# Weight-X.net
KiCad netlist of a schematic drawn in EAGLE
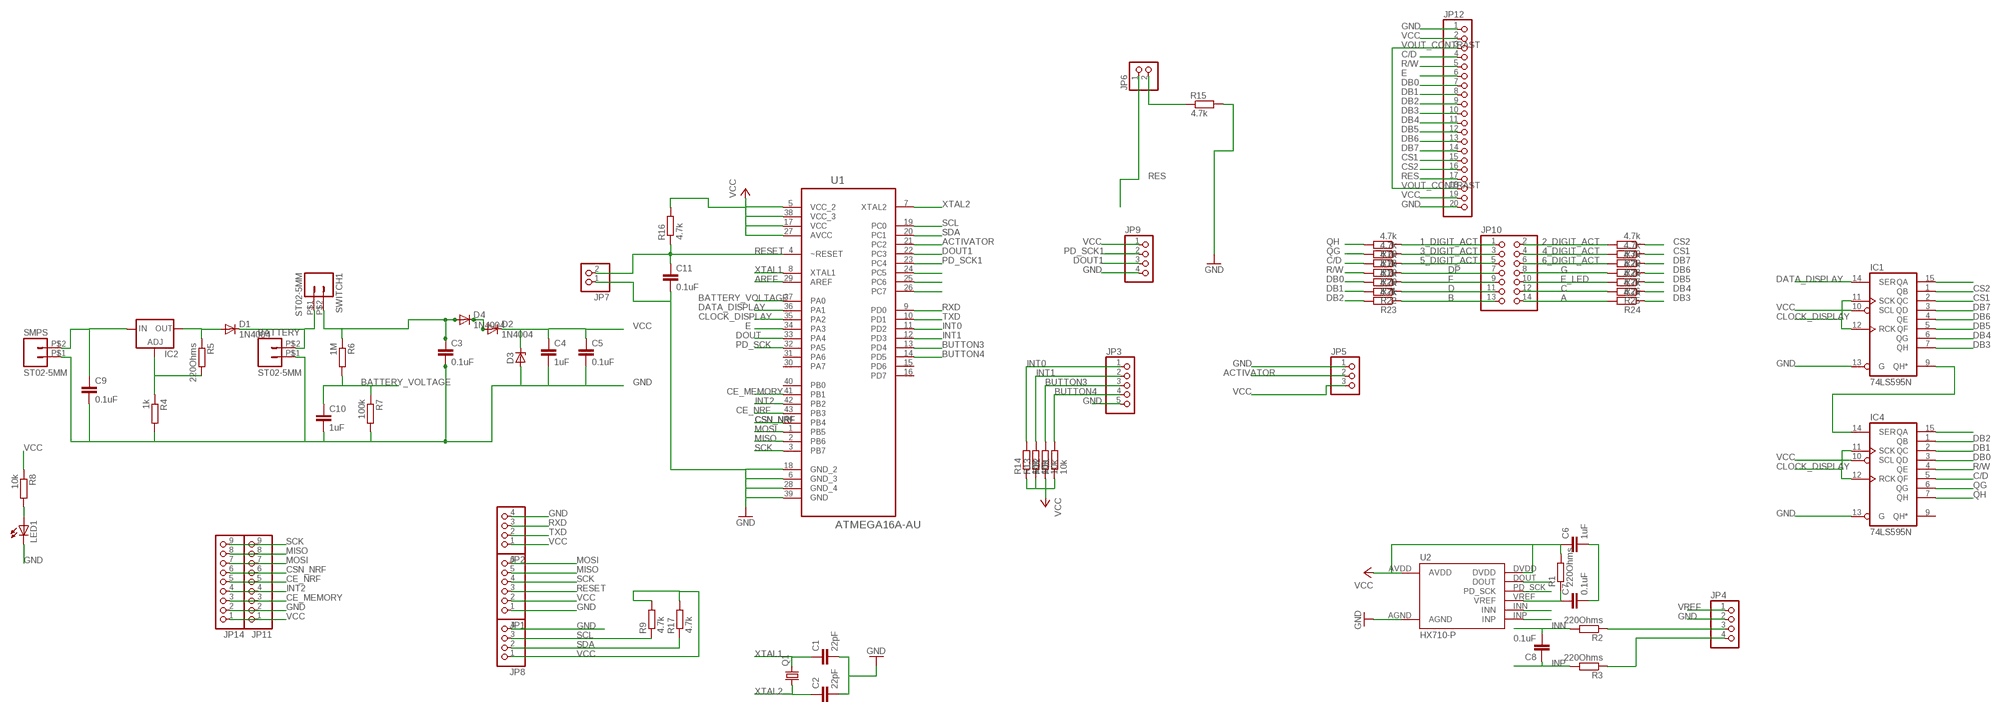
[diagram p0: schematic, sheet 1]

(export (version "E")
  (design (tool "Eeschema 10.0.6"))
  (components
    (comp (ref "BATTERY")
      (value "ST02-5MM")
      (footprint "eagle-import:EK500V-02P")
      (libsource (lib "eagle-import") (part "ST02-5MM"))
    )
    (comp (ref "C1")
      (value "22pF")
      (footprint "eagle-import:C2.5-2")
      (libsource (lib "eagle-import") (part "C2.5/2"))
    )
    (comp (ref "C2")
      (value "22pF")
      (footprint "eagle-import:C2.5-2")
      (libsource (lib "eagle-import") (part "C2.5/2"))
    )
    (comp (ref "C3")
      (value "0.1uF")
      (footprint "eagle-import:C5B2.5")
      (libsource (lib "eagle-import") (part "C5/2.5"))
    )
    (comp (ref "C4")
      (value "1uF")
      (footprint "eagle-import:C5B2.5")
      (libsource (lib "eagle-import") (part "C5/2.5"))
    )
    (comp (ref "C5")
      (value "0.1uF")
      (footprint "eagle-import:C5B2.5")
      (libsource (lib "eagle-import") (part "C5/2.5"))
    )
    (comp (ref "C6")
      (value "1uF")
      (footprint "eagle-import:C5B2.5")
      (libsource (lib "eagle-import") (part "C5/2.5"))
    )
    (comp (ref "C7")
      (value "0.1uF")
      (footprint "eagle-import:C5B2.5")
      (libsource (lib "eagle-import") (part "C5/2.5"))
    )
    (comp (ref "C8")
      (value "0.1uF")
      (footprint "eagle-import:C5B2.5")
      (libsource (lib "eagle-import") (part "C5/2.5"))
    )
    (comp (ref "C9")
      (value "0.1uF")
      (footprint "eagle-import:C5B2.5")
      (libsource (lib "eagle-import") (part "C5/2.5"))
    )
    (comp (ref "C10")
      (value "1uF")
      (footprint "eagle-import:C5B2.5")
      (libsource (lib "eagle-import") (part "C5/2.5"))
    )
    (comp (ref "C11")
      (value "0.1uF")
      (footprint "eagle-import:C5B2.5")
      (libsource (lib "eagle-import") (part "C5/2.5"))
    )
    (comp (ref "D1")
      (value "1N4004")
      (footprint "eagle-import:DO41-10")
      (libsource (lib "eagle-import") (part "1N4004"))
    )
    (comp (ref "D2")
      (value "1N4004")
      (footprint "eagle-import:DO41-10")
      (libsource (lib "eagle-import") (part "diode_1N4004"))
    )
    (comp (ref "D3")
      (value "ZENER-DIODEC1702-15")
      (footprint "eagle-import:C1702-15")
      (libsource (lib "eagle-import") (part "ZENER-DIODEC1702-15"))
    )
    (comp (ref "D4")
      (value "1N4004")
      (footprint "eagle-import:DO41-10")
      (libsource (lib "eagle-import") (part "diode_1N4004"))
    )
    (comp (ref "IC1")
      (value "74LS595N")
      (footprint "eagle-import:DIL16")
      (libsource (lib "eagle-import") (part "74595NLS"))
    )
    (comp (ref "IC2")
      (value "LM317TS")
      (footprint "eagle-import:317TS")
      (libsource (lib "eagle-import") (part "LM317TS"))
    )
    (comp (ref "IC4")
      (value "74LS595N")
      (footprint "eagle-import:DIL16")
      (libsource (lib "eagle-import") (part "74595NLS"))
    )
    (comp (ref "JP1")
      (value "PINHD-1X6")
      (footprint "eagle-import:1X06")
      (libsource (lib "eagle-import") (part "PINHD-1X6"))
    )
    (comp (ref "JP2")
      (value "PINHD-1X4")
      (footprint "eagle-import:1X04")
      (libsource (lib "eagle-import") (part "PINHD-1X4"))
    )
    (comp (ref "JP3")
      (value "PINHD-1X5")
      (footprint "eagle-import:1X05")
      (libsource (lib "eagle-import") (part "PINHD-1X5"))
    )
    (comp (ref "JP4")
      (value "PINHD-1X4")
      (footprint "eagle-import:1X04")
      (libsource (lib "eagle-import") (part "PINHD-1X4"))
    )
    (comp (ref "JP5")
      (value "PINHD-1X3")
      (footprint "eagle-import:1X03")
      (libsource (lib "eagle-import") (part "PINHD-1X3"))
    )
    (comp (ref "JP6")
      (value "PINHD-1X2")
      (footprint "eagle-import:1X02")
      (libsource (lib "eagle-import") (part "PINHD-1X2"))
    )
    (comp (ref "JP7")
      (value "PINHD-1X2")
      (footprint "eagle-import:1X02")
      (libsource (lib "eagle-import") (part "PINHD-1X2"))
    )
    (comp (ref "JP8")
      (value "PINHD-1X4")
      (footprint "eagle-import:1X04")
      (libsource (lib "eagle-import") (part "PINHD-1X4"))
    )
    (comp (ref "JP9")
      (value "PINHD-1X4")
      (footprint "eagle-import:1X04")
      (libsource (lib "eagle-import") (part "PINHD-1X4"))
    )
    (comp (ref "JP10")
      (value "PINHD-2X7")
      (footprint "eagle-import:2X07")
      (libsource (lib "eagle-import") (part "PINHD-2X7"))
    )
    (comp (ref "JP11")
      (value "PINHD-1X9")
      (footprint "eagle-import:1X09")
      (libsource (lib "eagle-import") (part "PINHD-1X9"))
    )
    (comp (ref "JP12")
      (value "PINHD-1X20")
      (footprint "eagle-import:1X20")
      (libsource (lib "eagle-import") (part "PINHD-1X20"))
    )
    (comp (ref "JP14")
      (value "PINHD-1X9")
      (footprint "eagle-import:1X09")
      (libsource (lib "eagle-import") (part "PINHD-1X9"))
    )
    (comp (ref "LED1")
      (value "LED5MM")
      (footprint "eagle-import:LED5MM")
      (libsource (lib "eagle-import") (part "LED5MM"))
    )
    (comp (ref "Q1")
      (value "CRYSTALHC49U-V")
      (footprint "eagle-import:HC49U-V")
      (libsource (lib "eagle-import") (part "CRYSTALHC49U-V"))
    )
    (comp (ref "R1")
      (value "220Ohms")
      (footprint "eagle-import:0204_7")
      (libsource (lib "eagle-import") (part "R0204/7"))
    )
    (comp (ref "R2")
      (value "220Ohms")
      (footprint "eagle-import:0204_7")
      (libsource (lib "eagle-import") (part "R0204/7"))
    )
    (comp (ref "R3")
      (value "220Ohms")
      (footprint "eagle-import:0204_7")
      (libsource (lib "eagle-import") (part "R0204/7"))
    )
    (comp (ref "R4")
      (value "1k")
      (footprint "eagle-import:0204_7")
      (libsource (lib "eagle-import") (part "R0204/7"))
    )
    (comp (ref "R5")
      (value "220Ohms")
      (footprint "eagle-import:0204_7")
      (libsource (lib "eagle-import") (part "R0204/7"))
    )
    (comp (ref "R6")
      (value "1M")
      (footprint "eagle-import:0204_7")
      (libsource (lib "eagle-import") (part "R0204/7"))
    )
    (comp (ref "R7")
      (value "100k")
      (footprint "eagle-import:0204_7")
      (libsource (lib "eagle-import") (part "R0204/7"))
    )
    (comp (ref "R8")
      (value "10k")
      (footprint "eagle-import:0204_7")
      (libsource (lib "eagle-import") (part "R0204/7"))
    )
    (comp (ref "R9")
      (value "4.7k")
      (footprint "eagle-import:0204_7")
      (libsource (lib "eagle-import") (part "R0204/7"))
    )
    (comp (ref "R10")
      (value "4.7k")
      (footprint "eagle-import:0204_7")
      (libsource (lib "eagle-import") (part "R0204/7"))
    )
    (comp (ref "R11")
      (value "10k")
      (footprint "eagle-import:0204_7")
      (libsource (lib "eagle-import") (part "R0204/7"))
    )
    (comp (ref "R12")
      (value "10k")
      (footprint "eagle-import:0204_7")
      (libsource (lib "eagle-import") (part "R0204/7"))
    )
    (comp (ref "R13")
      (value "10k")
      (footprint "eagle-import:0204_7")
      (libsource (lib "eagle-import") (part "R0204/7"))
    )
    (comp (ref "R14")
      (value "10k")
      (footprint "eagle-import:0204_7")
      (libsource (lib "eagle-import") (part "R0204/7"))
    )
    (comp (ref "R15")
      (value "4.7k")
      (footprint "eagle-import:0204_7")
      (libsource (lib "eagle-import") (part "R0204/7"))
    )
    (comp (ref "R16")
      (value "4.7k")
      (footprint "eagle-import:0204_7")
      (libsource (lib "eagle-import") (part "R0204/7"))
    )
    (comp (ref "R17")
      (value "4.7k")
      (footprint "eagle-import:0204_7")
      (libsource (lib "eagle-import") (part "R0204/7"))
    )
    (comp (ref "R18")
      (value "4.7k")
      (footprint "eagle-import:0204_7")
      (libsource (lib "eagle-import") (part "R0204/7"))
    )
    (comp (ref "R19")
      (value "4.7k")
      (footprint "eagle-import:0204_7")
      (libsource (lib "eagle-import") (part "R0204/7"))
    )
    (comp (ref "R20")
      (value "4.7k")
      (footprint "eagle-import:0204_7")
      (libsource (lib "eagle-import") (part "R0204/7"))
    )
    (comp (ref "R21")
      (value "4.7k")
      (footprint "eagle-import:0204_7")
      (libsource (lib "eagle-import") (part "R0204/7"))
    )
    (comp (ref "R22")
      (value "4.7k")
      (footprint "eagle-import:0204_7")
      (libsource (lib "eagle-import") (part "R0204/7"))
    )
    (comp (ref "R23")
      (value "4.7k")
      (footprint "eagle-import:0204_7")
      (libsource (lib "eagle-import") (part "R0204/7"))
    )
    (comp (ref "R24")
      (value "4.7k")
      (footprint "eagle-import:0204_7")
      (libsource (lib "eagle-import") (part "R0204/7"))
    )
    (comp (ref "R25")
      (value "4.7k")
      (footprint "eagle-import:0204_7")
      (libsource (lib "eagle-import") (part "R0204/7"))
    )
    (comp (ref "R26")
      (value "4.7k")
      (footprint "eagle-import:0204_7")
      (libsource (lib "eagle-import") (part "R0204/7"))
    )
    (comp (ref "R27")
      (value "4.7k")
      (footprint "eagle-import:0204_7")
      (libsource (lib "eagle-import") (part "R0204/7"))
    )
    (comp (ref "R28")
      (value "4.7k")
      (footprint "eagle-import:0204_7")
      (libsource (lib "eagle-import") (part "R0204/7"))
    )
    (comp (ref "R29")
      (value "4.7k")
      (footprint "eagle-import:0204_7")
      (libsource (lib "eagle-import") (part "R0204/7"))
    )
    (comp (ref "R30")
      (value "4.7k")
      (footprint "eagle-import:0204_7")
      (libsource (lib "eagle-import") (part "R0204/7"))
    )
    (comp (ref "SMPS")
      (value "ST02-5MM")
      (footprint "eagle-import:EK500V-02P")
      (libsource (lib "eagle-import") (part "ST02-5MM"))
    )
    (comp (ref "SWITCH1")
      (value "ST02-5MM")
      (footprint "eagle-import:EK500V-02P")
      (libsource (lib "eagle-import") (part "ST02-5MM"))
    )
    (comp (ref "U1")
      (value "ATMEGA16A-AU")
      (footprint "eagle-import:QFP80P1200X1200X120-44N")
      (libsource (lib "eagle-import") (part "ATMEGA16A-AU"))
    )
    (comp (ref "U2")
      (value "HX710-P")
      (footprint "eagle-import:PDIP08_300MIL")
      (libsource (lib "eagle-import") (part "HX710P-"))
    )
  )
  (nets
    (net (code "1") (name "/1_DIGIT_ACT") (class "Default")
      (node (ref "JP10") (pin "1") (pinfunction "1_1") (pintype "passive"))
      (node (ref "R10") (pin "1") (pinfunction "1_1") (pintype "passive"))
    )
    (net (code "2") (name "/2_DIGIT_ACT") (class "Default")
      (node (ref "JP10") (pin "2") (pinfunction "2_2") (pintype "passive"))
      (node (ref "R30") (pin "2") (pinfunction "2_2") (pintype "passive"))
    )
    (net (code "3") (name "/3_DIGIT_ACT") (class "Default")
      (node (ref "JP10") (pin "3") (pinfunction "3_3") (pintype "passive"))
      (node (ref "R18") (pin "1") (pinfunction "1_1") (pintype "passive"))
    )
    (net (code "4") (name "/4_DIGIT_ACT") (class "Default")
      (node (ref "JP10") (pin "4") (pinfunction "4_4") (pintype "passive"))
      (node (ref "R29") (pin "2") (pinfunction "2_2") (pintype "passive"))
    )
    (net (code "5") (name "/5_DIGIT_ACT") (class "Default")
      (node (ref "JP10") (pin "5") (pinfunction "5_5") (pintype "passive"))
      (node (ref "R19") (pin "1") (pinfunction "1_1") (pintype "passive"))
    )
    (net (code "6") (name "/6_DIGIT_ACT") (class "Default")
      (node (ref "JP10") (pin "6") (pinfunction "6_6") (pintype "passive"))
      (node (ref "R28") (pin "2") (pinfunction "2_2") (pintype "passive"))
    )
    (net (code "7") (name "/A") (class "Default")
      (node (ref "JP10") (pin "14") (pinfunction "14_14") (pintype "passive"))
      (node (ref "R24") (pin "2") (pinfunction "2_2") (pintype "passive"))
    )
    (net (code "8") (name "/ACTIVATOR") (class "Default")
      (node (ref "JP5") (pin "2") (pinfunction "2_2") (pintype "passive"))
      (node (ref "U1") (pin "21") (pinfunction "PC2_21") (pintype "bidirectional"))
    )
    (net (code "9") (name "/AREF") (class "Default")
      (node (ref "U1") (pin "29") (pinfunction "AREF_29") (pintype "input"))
    )
    (net (code "10") (name "/B") (class "Default")
      (node (ref "JP10") (pin "13") (pinfunction "13_13") (pintype "passive"))
      (node (ref "R23") (pin "1") (pinfunction "1_1") (pintype "passive"))
    )
    (net (code "11") (name "/BATTERY_VOLTAGE") (class "Default")
      (node (ref "C10") (pin "1") (pinfunction "1_1") (pintype "passive"))
      (node (ref "R6") (pin "2") (pinfunction "2_2") (pintype "passive"))
      (node (ref "R7") (pin "1") (pinfunction "1_1") (pintype "passive"))
      (node (ref "U1") (pin "37") (pinfunction "PA0_37") (pintype "bidirectional"))
    )
    (net (code "12") (name "/BUTTON3") (class "Default")
      (node (ref "JP3") (pin "3") (pinfunction "3_3") (pintype "passive"))
      (node (ref "R12") (pin "2") (pinfunction "2_2") (pintype "passive"))
      (node (ref "U1") (pin "13") (pinfunction "PD4_13") (pintype "bidirectional"))
    )
    (net (code "13") (name "/BUTTON4") (class "Default")
      (node (ref "JP3") (pin "4") (pinfunction "4_4") (pintype "passive"))
      (node (ref "R11") (pin "2") (pinfunction "2_2") (pintype "passive"))
      (node (ref "U1") (pin "14") (pinfunction "PD5_14") (pintype "bidirectional"))
    )
    (net (code "14") (name "/C") (class "Default")
      (node (ref "JP10") (pin "12") (pinfunction "12_12") (pintype "passive"))
      (node (ref "R25") (pin "2") (pinfunction "2_2") (pintype "passive"))
    )
    (net (code "15") (name "/CE_MEMORY") (class "Default")
      (node (ref "JP11") (pin "3") (pinfunction "3_3") (pintype "passive"))
      (node (ref "JP14") (pin "3") (pinfunction "3_3") (pintype "passive"))
      (node (ref "U1") (pin "41") (pinfunction "PB1_41") (pintype "bidirectional"))
    )
    (net (code "16") (name "/CE_NRF") (class "Default")
      (node (ref "JP11") (pin "5") (pinfunction "5_5") (pintype "passive"))
      (node (ref "JP14") (pin "5") (pinfunction "5_5") (pintype "passive"))
      (node (ref "U1") (pin "43") (pinfunction "PB3_43") (pintype "bidirectional"))
    )
    (net (code "17") (name "/CLOCK_DISPLAY") (class "Default")
      (node (ref "IC1") (pin "11") (pinfunction "SCK_11") (pintype "input"))
      (node (ref "IC1") (pin "12") (pinfunction "RCK_12") (pintype "input"))
      (node (ref "IC4") (pin "11") (pinfunction "SCK_11") (pintype "input"))
      (node (ref "IC4") (pin "12") (pinfunction "RCK_12") (pintype "input"))
      (node (ref "U1") (pin "35") (pinfunction "PA2_35") (pintype "bidirectional"))
    )
    (net (code "18") (name "/CS1") (class "Default")
      (node (ref "IC1") (pin "2") (pinfunction "QC_2") (pintype "tri_state"))
      (node (ref "JP12") (pin "15") (pinfunction "15_15") (pintype "passive"))
      (node (ref "R29") (pin "1") (pinfunction "1_1") (pintype "passive"))
    )
    (net (code "19") (name "/CS2") (class "Default")
      (node (ref "IC1") (pin "1") (pinfunction "QB_1") (pintype "tri_state"))
      (node (ref "JP12") (pin "16") (pinfunction "16_16") (pintype "passive"))
      (node (ref "R30") (pin "1") (pinfunction "1_1") (pintype "passive"))
    )
    (net (code "20") (name "/CSN_NRF") (class "Default")
      (node (ref "JP11") (pin "6") (pinfunction "6_6") (pintype "passive"))
      (node (ref "JP14") (pin "6") (pinfunction "6_6") (pintype "passive"))
      (node (ref "U1") (pin "44") (pinfunction "PB4_44") (pintype "bidirectional"))
    )
    (net (code "21") (name "/C{slash}D") (class "Default")
      (node (ref "IC4") (pin "5") (pinfunction "QF_5") (pintype "tri_state"))
      (node (ref "JP12") (pin "4") (pinfunction "4_4") (pintype "passive"))
      (node (ref "R19") (pin "2") (pinfunction "2_2") (pintype "passive"))
    )
    (net (code "22") (name "/D") (class "Default")
      (node (ref "JP10") (pin "11") (pinfunction "11_11") (pintype "passive"))
      (node (ref "R22") (pin "1") (pinfunction "1_1") (pintype "passive"))
    )
    (net (code "23") (name "/DATA_DISPLAY") (class "Default")
      (node (ref "IC1") (pin "14") (pinfunction "SER_14") (pintype "input"))
      (node (ref "U1") (pin "36") (pinfunction "PA1_36") (pintype "bidirectional"))
    )
    (net (code "24") (name "/DB0") (class "Default")
      (node (ref "IC4") (pin "3") (pinfunction "QD_3") (pintype "tri_state"))
      (node (ref "JP12") (pin "7") (pinfunction "7_7") (pintype "passive"))
      (node (ref "R21") (pin "2") (pinfunction "2_2") (pintype "passive"))
    )
    (net (code "25") (name "/DB1") (class "Default")
      (node (ref "IC4") (pin "2") (pinfunction "QC_2") (pintype "tri_state"))
      (node (ref "JP12") (pin "8") (pinfunction "8_8") (pintype "passive"))
      (node (ref "R22") (pin "2") (pinfunction "2_2") (pintype "passive"))
    )
    (net (code "26") (name "/DB2") (class "Default")
      (node (ref "IC4") (pin "1") (pinfunction "QB_1") (pintype "tri_state"))
      (node (ref "JP12") (pin "9") (pinfunction "9_9") (pintype "passive"))
      (node (ref "R23") (pin "2") (pinfunction "2_2") (pintype "passive"))
    )
    (net (code "27") (name "/DB3") (class "Default")
      (node (ref "IC1") (pin "7") (pinfunction "QH_7") (pintype "tri_state"))
      (node (ref "JP12") (pin "10") (pinfunction "10_10") (pintype "passive"))
      (node (ref "R24") (pin "1") (pinfunction "1_1") (pintype "passive"))
    )
    (net (code "28") (name "/DB4") (class "Default")
      (node (ref "IC1") (pin "6") (pinfunction "QG_6") (pintype "tri_state"))
      (node (ref "JP12") (pin "11") (pinfunction "11_11") (pintype "passive"))
      (node (ref "R25") (pin "1") (pinfunction "1_1") (pintype "passive"))
    )
    (net (code "29") (name "/DB5") (class "Default")
      (node (ref "IC1") (pin "5") (pinfunction "QF_5") (pintype "tri_state"))
      (node (ref "JP12") (pin "12") (pinfunction "12_12") (pintype "passive"))
      (node (ref "R26") (pin "1") (pinfunction "1_1") (pintype "passive"))
    )
    (net (code "30") (name "/DB6") (class "Default")
      (node (ref "IC1") (pin "4") (pinfunction "QE_4") (pintype "tri_state"))
      (node (ref "JP12") (pin "13") (pinfunction "13_13") (pintype "passive"))
      (node (ref "R27") (pin "1") (pinfunction "1_1") (pintype "passive"))
    )
    (net (code "31") (name "/DB7") (class "Default")
      (node (ref "IC1") (pin "3") (pinfunction "QD_3") (pintype "tri_state"))
      (node (ref "JP12") (pin "14") (pinfunction "14_14") (pintype "passive"))
      (node (ref "R28") (pin "1") (pinfunction "1_1") (pintype "passive"))
    )
    (net (code "32") (name "/DOUT") (class "Default")
      (node (ref "U1") (pin "33") (pinfunction "PA4_33") (pintype "bidirectional"))
      (node (ref "U2") (pin "DOUT") (pinfunction "DOUT_DOUT") (pintype "bidirectional"))
    )
    (net (code "33") (name "/DOUT1") (class "Default")
      (node (ref "JP9") (pin "3") (pinfunction "3_3") (pintype "passive"))
      (node (ref "U1") (pin "22") (pinfunction "PC3_22") (pintype "bidirectional"))
    )
    (net (code "34") (name "/DP") (class "Default")
      (node (ref "JP10") (pin "7") (pinfunction "7_7") (pintype "passive"))
      (node (ref "R20") (pin "1") (pinfunction "1_1") (pintype "passive"))
    )
    (net (code "35") (name "/E") (class "Default")
      (node (ref "JP12") (pin "6") (pinfunction "6_6") (pintype "passive"))
      (node (ref "U1") (pin "34") (pinfunction "PA3_34") (pintype "bidirectional"))
    )
    (net (code "36") (name "/E_LED") (class "Default")
      (node (ref "JP10") (pin "10") (pinfunction "10_10") (pintype "passive"))
      (node (ref "R26") (pin "2") (pinfunction "2_2") (pintype "passive"))
    )
    (net (code "37") (name "/F") (class "Default")
      (node (ref "JP10") (pin "9") (pinfunction "9_9") (pintype "passive"))
      (node (ref "R21") (pin "1") (pinfunction "1_1") (pintype "passive"))
    )
    (net (code "38") (name "/G") (class "Default")
      (node (ref "JP10") (pin "8") (pinfunction "8_8") (pintype "passive"))
      (node (ref "R27") (pin "2") (pinfunction "2_2") (pintype "passive"))
    )
    (net (code "39") (name "/INN") (class "Default")
      (node (ref "C8") (pin "2") (pinfunction "2_2") (pintype "passive"))
      (node (ref "R2") (pin "2") (pinfunction "2_2") (pintype "passive"))
      (node (ref "U2") (pin "INN") (pinfunction "INN_INN") (pintype "bidirectional"))
    )
    (net (code "40") (name "/INP") (class "Default")
      (node (ref "C8") (pin "1") (pinfunction "1_1") (pintype "passive"))
      (node (ref "R3") (pin "2") (pinfunction "2_2") (pintype "passive"))
      (node (ref "U2") (pin "INP") (pinfunction "INP_INP") (pintype "bidirectional"))
    )
    (net (code "41") (name "/INT0") (class "Default")
      (node (ref "JP3") (pin "1") (pinfunction "1_1") (pintype "passive"))
      (node (ref "R14") (pin "2") (pinfunction "2_2") (pintype "passive"))
      (node (ref "U1") (pin "11") (pinfunction "PD2_11") (pintype "bidirectional"))
    )
    (net (code "42") (name "/INT1") (class "Default")
      (node (ref "JP3") (pin "2") (pinfunction "2_2") (pintype "passive"))
      (node (ref "R13") (pin "2") (pinfunction "2_2") (pintype "passive"))
      (node (ref "U1") (pin "12") (pinfunction "PD3_12") (pintype "bidirectional"))
    )
    (net (code "43") (name "/INT2") (class "Default")
      (node (ref "JP11") (pin "4") (pinfunction "4_4") (pintype "passive"))
      (node (ref "JP14") (pin "4") (pinfunction "4_4") (pintype "passive"))
      (node (ref "U1") (pin "42") (pinfunction "PB2_42") (pintype "bidirectional"))
    )
    (net (code "44") (name "/MISO") (class "Default")
      (node (ref "JP1") (pin "5") (pinfunction "5_5") (pintype "passive"))
      (node (ref "JP11") (pin "8") (pinfunction "8_8") (pintype "passive"))
      (node (ref "JP14") (pin "8") (pinfunction "8_8") (pintype "passive"))
      (node (ref "U1") (pin "2") (pinfunction "PB6_2") (pintype "bidirectional"))
    )
    (net (code "45") (name "/MOSI") (class "Default")
      (node (ref "JP1") (pin "6") (pinfunction "6_6") (pintype "passive"))
      (node (ref "JP11") (pin "7") (pinfunction "7_7") (pintype "passive"))
      (node (ref "JP14") (pin "7") (pinfunction "7_7") (pintype "passive"))
      (node (ref "U1") (pin "1") (pinfunction "PB5_1") (pintype "bidirectional"))
    )
    (net (code "46") (name "/PD_SCK") (class "Default")
      (node (ref "U1") (pin "32") (pinfunction "PA5_32") (pintype "bidirectional"))
      (node (ref "U2") (pin "PD_SCK") (pinfunction "PD_SCK_PD_SCK") (pintype "bidirectional"))
    )
    (net (code "47") (name "/PD_SCK1") (class "Default")
      (node (ref "JP9") (pin "2") (pinfunction "2_2") (pintype "passive"))
      (node (ref "U1") (pin "23") (pinfunction "PC4_23") (pintype "bidirectional"))
    )
    (net (code "48") (name "/QG") (class "Default")
      (node (ref "IC4") (pin "6") (pinfunction "QG_6") (pintype "tri_state"))
      (node (ref "R18") (pin "2") (pinfunction "2_2") (pintype "passive"))
    )
    (net (code "49") (name "/QH") (class "Default")
      (node (ref "IC4") (pin "7") (pinfunction "QH_7") (pintype "tri_state"))
      (node (ref "R10") (pin "2") (pinfunction "2_2") (pintype "passive"))
    )
    (net (code "50") (name "/RES") (class "Default")
      (node (ref "JP12") (pin "17") (pinfunction "17_17") (pintype "passive"))
      (node (ref "JP6") (pin "1") (pinfunction "1_1") (pintype "passive"))
    )
    (net (code "51") (name "/RESET") (class "Default")
      (node (ref "C11") (pin "1") (pinfunction "1_1") (pintype "passive"))
      (node (ref "JP1") (pin "3") (pinfunction "3_3") (pintype "passive"))
      (node (ref "JP7") (pin "2") (pinfunction "2_2") (pintype "passive"))
      (node (ref "R16") (pin "1") (pinfunction "1_1") (pintype "passive"))
      (node (ref "U1") (pin "4") (pinfunction "~{RESET}_4") (pintype "input"))
    )
    (net (code "52") (name "/RXD") (class "Default")
      (node (ref "JP2") (pin "3") (pinfunction "3_3") (pintype "passive"))
      (node (ref "U1") (pin "9") (pinfunction "PD0_9") (pintype "bidirectional"))
    )
    (net (code "53") (name "/R{slash}W") (class "Default")
      (node (ref "IC4") (pin "4") (pinfunction "QE_4") (pintype "tri_state"))
      (node (ref "JP12") (pin "5") (pinfunction "5_5") (pintype "passive"))
      (node (ref "R20") (pin "2") (pinfunction "2_2") (pintype "passive"))
    )
    (net (code "54") (name "/SCK") (class "Default")
      (node (ref "JP1") (pin "4") (pinfunction "4_4") (pintype "passive"))
      (node (ref "JP11") (pin "9") (pinfunction "9_9") (pintype "passive"))
      (node (ref "JP14") (pin "9") (pinfunction "9_9") (pintype "passive"))
      (node (ref "U1") (pin "3") (pinfunction "PB7_3") (pintype "bidirectional"))
    )
    (net (code "55") (name "/SCL") (class "Default")
      (node (ref "JP8") (pin "3") (pinfunction "3_3") (pintype "passive"))
      (node (ref "R9") (pin "1") (pinfunction "1_1") (pintype "passive"))
      (node (ref "U1") (pin "19") (pinfunction "PC0_19") (pintype "bidirectional"))
    )
    (net (code "56") (name "/SDA") (class "Default")
      (node (ref "JP8") (pin "2") (pinfunction "2_2") (pintype "passive"))
      (node (ref "R17") (pin "1") (pinfunction "1_1") (pintype "passive"))
      (node (ref "U1") (pin "20") (pinfunction "PC1_20") (pintype "bidirectional"))
    )
    (net (code "57") (name "/TXD") (class "Default")
      (node (ref "JP2") (pin "2") (pinfunction "2_2") (pintype "passive"))
      (node (ref "U1") (pin "10") (pinfunction "PD1_10") (pintype "bidirectional"))
    )
    (net (code "58") (name "/VOUT_CONTRAST") (class "Default")
      (node (ref "JP12") (pin "18") (pinfunction "18_18") (pintype "passive"))
      (node (ref "JP12") (pin "3") (pinfunction "3_3") (pintype "passive"))
    )
    (net (code "59") (name "/VREF") (class "Default")
      (node (ref "C7") (pin "1") (pinfunction "1_1") (pintype "passive"))
      (node (ref "JP4") (pin "1") (pinfunction "1_1") (pintype "passive"))
      (node (ref "R1") (pin "1") (pinfunction "1_1") (pintype "passive"))
      (node (ref "U2") (pin "VREF") (pinfunction "VREF_VREF") (pintype "bidirectional"))
    )
    (net (code "60") (name "/XTAL1") (class "Default")
      (node (ref "C1") (pin "1") (pinfunction "1_1") (pintype "passive"))
      (node (ref "Q1") (pin "2") (pinfunction "2_2") (pintype "passive"))
      (node (ref "U1") (pin "8") (pinfunction "XTAL1_8") (pintype "input"))
    )
    (net (code "61") (name "/XTAL2") (class "Default")
      (node (ref "C2") (pin "1") (pinfunction "1_1") (pintype "passive"))
      (node (ref "Q1") (pin "1") (pinfunction "1_1") (pintype "passive"))
      (node (ref "U1") (pin "7") (pinfunction "XTAL2_7") (pintype "output"))
    )
    (net (code "62") (name "GND") (class "Default")
      (node (ref "BATTERY") (pin "P$1") (pinfunction "1_P$1") (pintype "passive"))
      (node (ref "C1") (pin "2") (pinfunction "2_2") (pintype "passive"))
      (node (ref "C10") (pin "2") (pinfunction "2_2") (pintype "passive"))
      (node (ref "C11") (pin "2") (pinfunction "2_2") (pintype "passive"))
      (node (ref "C2") (pin "2") (pinfunction "2_2") (pintype "passive"))
      (node (ref "C3") (pin "2") (pinfunction "2_2") (pintype "passive"))
      (node (ref "C4") (pin "2") (pinfunction "2_2") (pintype "passive"))
      (node (ref "C5") (pin "2") (pinfunction "2_2") (pintype "passive"))
      (node (ref "C6") (pin "2") (pinfunction "2_2") (pintype "passive"))
      (node (ref "C7") (pin "2") (pinfunction "2_2") (pintype "passive"))
      (node (ref "C9") (pin "2") (pinfunction "2_2") (pintype "passive"))
      (node (ref "D3") (pin "A") (pinfunction "A_A") (pintype "passive"))
      (node (ref "IC1") (pin "13") (pinfunction "G_13") (pintype "input"))
      (node (ref "IC4") (pin "13") (pinfunction "G_13") (pintype "input"))
      (node (ref "JP1") (pin "1") (pinfunction "1_1") (pintype "passive"))
      (node (ref "JP11") (pin "2") (pinfunction "2_2") (pintype "passive"))
      (node (ref "JP12") (pin "1") (pinfunction "1_1") (pintype "passive"))
      (node (ref "JP12") (pin "20") (pinfunction "20_20") (pintype "passive"))
      (node (ref "JP14") (pin "2") (pinfunction "2_2") (pintype "passive"))
      (node (ref "JP2") (pin "4") (pinfunction "4_4") (pintype "passive"))
      (node (ref "JP3") (pin "5") (pinfunction "5_5") (pintype "passive"))
      (node (ref "JP4") (pin "2") (pinfunction "2_2") (pintype "passive"))
      (node (ref "JP5") (pin "1") (pinfunction "1_1") (pintype "passive"))
      (node (ref "JP7") (pin "1") (pinfunction "1_1") (pintype "passive"))
      (node (ref "JP8") (pin "4") (pinfunction "4_4") (pintype "passive"))
      (node (ref "JP9") (pin "4") (pinfunction "4_4") (pintype "passive"))
      (node (ref "LED1") (pin "K") (pinfunction "C_K") (pintype "passive"))
      (node (ref "R15") (pin "2") (pinfunction "2_2") (pintype "passive"))
      (node (ref "R4") (pin "2") (pinfunction "2_2") (pintype "passive"))
      (node (ref "R7") (pin "2") (pinfunction "2_2") (pintype "passive"))
      (node (ref "SMPS") (pin "P$1") (pinfunction "1_P$1") (pintype "passive"))
      (node (ref "U1") (pin "18") (pinfunction "GND_2_18") (pintype "passive"))
      (node (ref "U1") (pin "28") (pinfunction "GND_4_28") (pintype "passive"))
      (node (ref "U1") (pin "39") (pinfunction "GND_39") (pintype "passive"))
      (node (ref "U1") (pin "6") (pinfunction "GND_3_6") (pintype "passive"))
      (node (ref "U2") (pin "AGND") (pinfunction "AGND_AGND") (pintype "power_in"))
    )
    (net (code "63") (name "Net-(BATTERY-2)") (class "Default")
      (node (ref "BATTERY") (pin "P$2") (pinfunction "2_P$2") (pintype "passive"))
      (node (ref "D1") (pin "C") (pinfunction "C_C") (pintype "passive"))
      (node (ref "SWITCH1") (pin "P$1") (pinfunction "1_P$1") (pintype "passive"))
    )
    (net (code "64") (name "Net-(D2-PadA)") (class "Default")
      (node (ref "D2") (pin "A") (pinfunction "A_A") (pintype "passive"))
      (node (ref "D4") (pin "C") (pinfunction "C_C") (pintype "passive"))
    )
    (net (code "65") (name "Net-(IC1A-QH*)") (class "Default")
      (node (ref "IC1") (pin "9") (pinfunction "QH*_9") (pintype "tri_state"))
      (node (ref "IC4") (pin "14") (pinfunction "SER_14") (pintype "input"))
    )
    (net (code "66") (name "Net-(IC2-ADJ)") (class "Default")
      (node (ref "IC2") (pin "1") (pinfunction "ADJ_1") (pintype "input"))
      (node (ref "R4") (pin "1") (pinfunction "1_1") (pintype "passive"))
      (node (ref "R5") (pin "2") (pinfunction "2_2") (pintype "passive"))
    )
    (net (code "67") (name "Net-(IC2-IN)") (class "Default")
      (node (ref "C9") (pin "1") (pinfunction "1_1") (pintype "passive"))
      (node (ref "IC2") (pin "3") (pinfunction "IN_3") (pintype "input"))
      (node (ref "SMPS") (pin "P$2") (pinfunction "2_P$2") (pintype "passive"))
    )
    (net (code "68") (name "Net-(IC2-OUT)") (class "Default")
      (node (ref "D1") (pin "A") (pinfunction "A_A") (pintype "passive"))
      (node (ref "IC2") (pin "2") (pinfunction "OUT_2") (pintype "passive"))
      (node (ref "R5") (pin "1") (pinfunction "1_1") (pintype "passive"))
    )
    (net (code "69") (name "Net-(JP4-Pad3)") (class "Default")
      (node (ref "JP4") (pin "3") (pinfunction "3_3") (pintype "passive"))
      (node (ref "R2") (pin "1") (pinfunction "1_1") (pintype "passive"))
    )
    (net (code "70") (name "Net-(JP4-Pad4)") (class "Default")
      (node (ref "JP4") (pin "4") (pinfunction "4_4") (pintype "passive"))
      (node (ref "R3") (pin "1") (pinfunction "1_1") (pintype "passive"))
    )
    (net (code "71") (name "Net-(JP6-Pad2)") (class "Default")
      (node (ref "JP6") (pin "2") (pinfunction "2_2") (pintype "passive"))
      (node (ref "R15") (pin "1") (pinfunction "1_1") (pintype "passive"))
    )
    (net (code "72") (name "Net-(LED1-PadA)") (class "Default")
      (node (ref "LED1") (pin "A") (pinfunction "A_A") (pintype "passive"))
      (node (ref "R8") (pin "2") (pinfunction "2_2") (pintype "passive"))
    )
    (net (code "73") (name "Net-(SWITCH1-2)") (class "Default")
      (node (ref "C3") (pin "1") (pinfunction "1_1") (pintype "passive"))
      (node (ref "D4") (pin "A") (pinfunction "A_A") (pintype "passive"))
      (node (ref "R6") (pin "1") (pinfunction "1_1") (pintype "passive"))
      (node (ref "SWITCH1") (pin "P$2") (pinfunction "2_P$2") (pintype "passive"))
    )
    (net (code "74") (name "VCC") (class "Default")
      (node (ref "C4") (pin "1") (pinfunction "1_1") (pintype "passive"))
      (node (ref "C5") (pin "1") (pinfunction "1_1") (pintype "passive"))
      (node (ref "C6") (pin "1") (pinfunction "1_1") (pintype "passive"))
      (node (ref "D2") (pin "C") (pinfunction "C_C") (pintype "passive"))
      (node (ref "D3") (pin "C") (pinfunction "C_C") (pintype "passive"))
      (node (ref "IC1") (pin "10") (pinfunction "SCL_10") (pintype "input"))
      (node (ref "IC4") (pin "10") (pinfunction "SCL_10") (pintype "input"))
      (node (ref "JP1") (pin "2") (pinfunction "2_2") (pintype "passive"))
      (node (ref "JP11") (pin "1") (pinfunction "1_1") (pintype "passive"))
      (node (ref "JP12") (pin "19") (pinfunction "19_19") (pintype "passive"))
      (node (ref "JP12") (pin "2") (pinfunction "2_2") (pintype "passive"))
      (node (ref "JP14") (pin "1") (pinfunction "1_1") (pintype "passive"))
      (node (ref "JP2") (pin "1") (pinfunction "1_1") (pintype "passive"))
      (node (ref "JP5") (pin "3") (pinfunction "3_3") (pintype "passive"))
      (node (ref "JP8") (pin "1") (pinfunction "1_1") (pintype "passive"))
      (node (ref "JP9") (pin "1") (pinfunction "1_1") (pintype "passive"))
      (node (ref "R1") (pin "2") (pinfunction "2_2") (pintype "passive"))
      (node (ref "R11") (pin "1") (pinfunction "1_1") (pintype "passive"))
      (node (ref "R12") (pin "1") (pinfunction "1_1") (pintype "passive"))
      (node (ref "R13") (pin "1") (pinfunction "1_1") (pintype "passive"))
      (node (ref "R14") (pin "1") (pinfunction "1_1") (pintype "passive"))
      (node (ref "R16") (pin "2") (pinfunction "2_2") (pintype "passive"))
      (node (ref "R17") (pin "2") (pinfunction "2_2") (pintype "passive"))
      (node (ref "R8") (pin "1") (pinfunction "1_1") (pintype "passive"))
      (node (ref "R9") (pin "2") (pinfunction "2_2") (pintype "passive"))
      (node (ref "U1") (pin "17") (pinfunction "VCC_17") (pintype "power_in"))
      (node (ref "U1") (pin "27") (pinfunction "AVCC_27") (pintype "power_in"))
      (node (ref "U1") (pin "38") (pinfunction "VCC_3_38") (pintype "power_in"))
      (node (ref "U1") (pin "5") (pinfunction "VCC_2_5") (pintype "power_in"))
      (node (ref "U2") (pin "AVDD") (pinfunction "AVDD_AVDD") (pintype "power_in"))
      (node (ref "U2") (pin "DVDD") (pinfunction "DVDD_DVDD") (pintype "bidirectional"))
    )
    (net (code "75") (name "unconnected-(IC1A-QA-Pad15)") (class "Default")
      (node (ref "IC1") (pin "15") (pinfunction "QA_15") (pintype "tri_state"))
    )
    (net (code "76") (name "unconnected-(IC4A-QA-Pad15)") (class "Default")
      (node (ref "IC4") (pin "15") (pinfunction "QA_15") (pintype "tri_state"))
    )
    (net (code "77") (name "unconnected-(IC4A-QH*-Pad9)") (class "Default")
      (node (ref "IC4") (pin "9") (pinfunction "QH*_9") (pintype "tri_state"))
    )
    (net (code "78") (name "unconnected-(U1-PA6-Pad31)") (class "Default")
      (node (ref "U1") (pin "31") (pinfunction "PA6_31") (pintype "bidirectional"))
    )
    (net (code "79") (name "unconnected-(U1-PA7-Pad30)") (class "Default")
      (node (ref "U1") (pin "30") (pinfunction "PA7_30") (pintype "bidirectional"))
    )
    (net (code "80") (name "unconnected-(U1-PB0-Pad40)") (class "Default")
      (node (ref "U1") (pin "40") (pinfunction "PB0_40") (pintype "bidirectional"))
    )
    (net (code "81") (name "unconnected-(U1-PC5-Pad24)") (class "Default")
      (node (ref "U1") (pin "24") (pinfunction "PC5_24") (pintype "bidirectional"))
    )
    (net (code "82") (name "unconnected-(U1-PC6-Pad25)") (class "Default")
      (node (ref "U1") (pin "25") (pinfunction "PC6_25") (pintype "bidirectional"))
    )
    (net (code "83") (name "unconnected-(U1-PC7-Pad26)") (class "Default")
      (node (ref "U1") (pin "26") (pinfunction "PC7_26") (pintype "bidirectional"))
    )
    (net (code "84") (name "unconnected-(U1-PD6-Pad15)") (class "Default")
      (node (ref "U1") (pin "15") (pinfunction "PD6_15") (pintype "bidirectional"))
    )
    (net (code "85") (name "unconnected-(U1-PD7-Pad16)") (class "Default")
      (node (ref "U1") (pin "16") (pinfunction "PD7_16") (pintype "bidirectional"))
    )
  )
)
